# MCU.net
KiCad netlist of a schematic drawn in Altium Designer
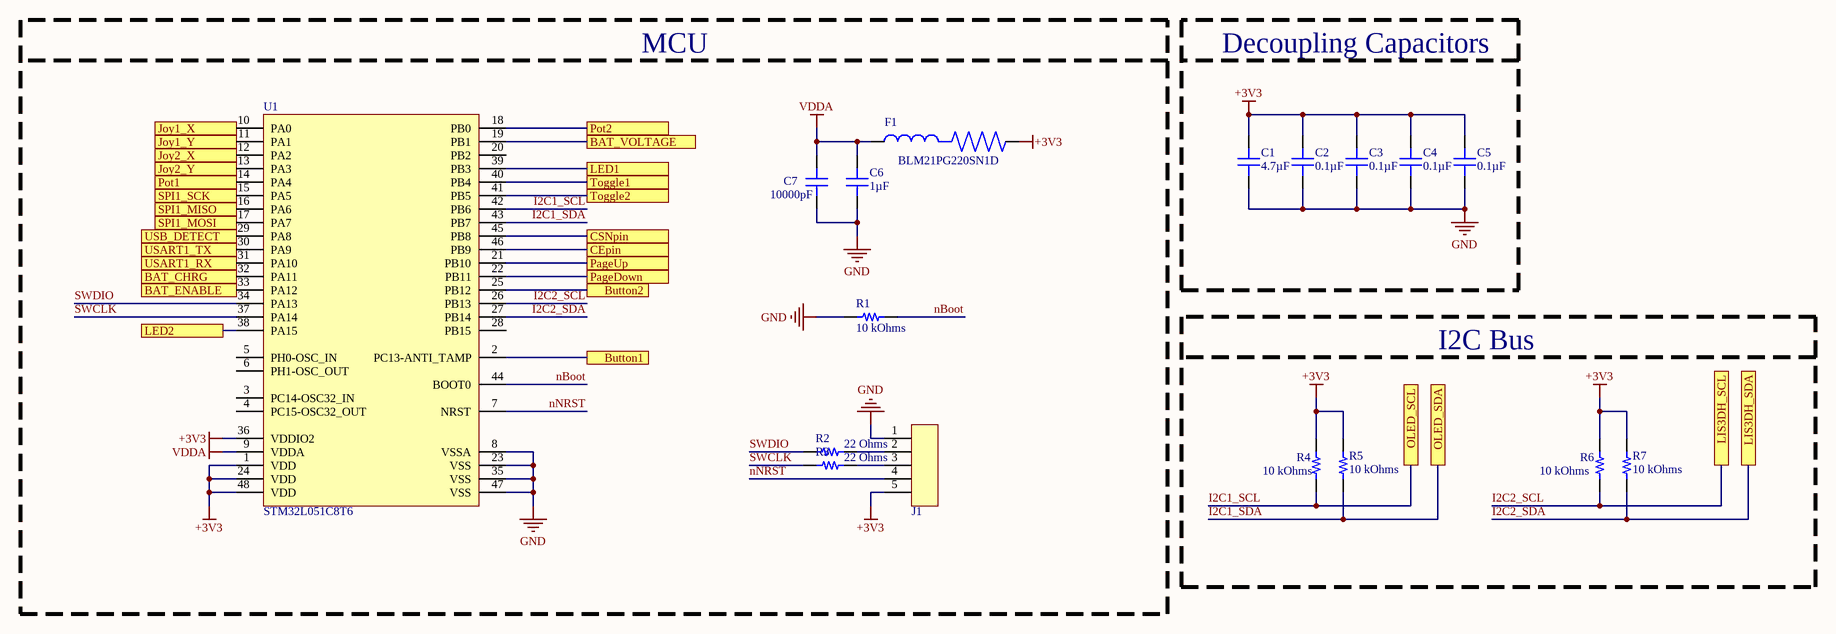
[diagram p0: MCU.SchDoc]

(export (version "E")
  (design (tool "Eeschema 10.0.6"))
  (components
    (comp (ref "C1")
      (value "4.7µF")
      (footprint "CAP 0603_1608")
      (description "CAP CER 4.7UF 10V X5R 0603")
      (fields (field (name "PART NUMBER") "LMK107BJ475KA-T") (field (name "MANUFACTURER") "Taiyo Yuden"))
      (libsource (lib "Celestial Altium Library - altium_library") (part "Capacitor"))
    )
    (comp (ref "C2")
      (value "0.1µF")
      (footprint "CAP 0603_1608")
      (description "CAP CER 0.10UF 16V X7R 0603")
      (fields (field (name "PART NUMBER") "0603Y0160104KXT") (field (name "MANUFACTURER") "Knowles Syfer"))
      (libsource (lib "Celestial Altium Library - altium_library") (part "Capacitor"))
    )
    (comp (ref "C3")
      (value "0.1µF")
      (footprint "CAP 0603_1608")
      (description "CAP CER 0.10UF 16V X7R 0603")
      (fields (field (name "PART NUMBER") "0603Y0160104KXT") (field (name "MANUFACTURER") "Knowles Syfer"))
      (libsource (lib "Celestial Altium Library - altium_library") (part "Capacitor"))
    )
    (comp (ref "C4")
      (value "0.1µF")
      (footprint "CAP 0603_1608")
      (description "CAP CER 0.10UF 16V X7R 0603")
      (fields (field (name "PART NUMBER") "0603Y0160104KXT") (field (name "MANUFACTURER") "Knowles Syfer"))
      (libsource (lib "Celestial Altium Library - altium_library") (part "Capacitor"))
    )
    (comp (ref "C5")
      (value "0.1µF")
      (footprint "CAP 0603_1608")
      (description "CAP CER 0.10UF 16V X7R 0603")
      (fields (field (name "PART NUMBER") "0603Y0160104KXT") (field (name "MANUFACTURER") "Knowles Syfer"))
      (libsource (lib "Celestial Altium Library - altium_library") (part "Capacitor"))
    )
    (comp (ref "C6")
      (value "1µF")
      (footprint "CAP 0603_1608")
      (description "CAP CER 0603 1UF 16V X7R 10%")
      (fields (field (name "PART NUMBER") "C0603C105K4RACAUTO") (field (name "MANUFACTURER") "KEMET"))
      (libsource (lib "Celestial Altium Library - altium_library") (part "Capacitor"))
    )
    (comp (ref "C7")
      (value "10000pF")
      (footprint "CAP 0603_1608")
      (description "CAP CER 0603 10NF 16V X7R 10%")
      (fields (field (name "PART NUMBER") "C0603C103K4RECAUTO") (field (name "MANUFACTURER") "KEMET"))
      (libsource (lib "Celestial Altium Library - altium_library") (part "Capacitor"))
    )
    (comp (ref "F1")
      (value "BLM21PG220SN1D")
      (footprint "BLM21PG220SN1D")
      (description "Ferrite Beads Multi-Layer 22Ohm 25% 100MHz 6A 9mOhm DCR 0805 Paper T/R")
      (fields (field (name "MANUFACTURER") "Murata") (field (name "TOLERANCE") "25%"))
      (libsource (lib "MyLibrary_Integrated") (part "BLM21PG220SN1D"))
    )
    (comp (ref "J1")
      (value "Header-90 Degree-5x1")
      (footprint "Header-90 Degree-5P")
      (libsource (lib "MyLibrary_Integrated") (part "Header-90 Degree-5x1"))
    )
    (comp (ref "R1")
      (value "10 kOhms")
      (footprint "RES 0603_1608")
      (description "RES 10K OHM 0.1% 1/16W 0603")
      (fields
        (field (name "PART NUMBER") "RNCS0603BKE10K0")
        (field (name "MANUFACTURER") "Stackpole Electronics Inc")
      )
      (libsource (lib "Celestial Altium Library - altium_library") (part "Resistor"))
    )
    (comp (ref "R2")
      (value "22 Ohms")
      (footprint "RES 0603_1608")
      (description "RES SMD 22 OHM 1% 1/10W 0603")
      (fields
        (field (name "PART NUMBER") "ERJ-3EKF22R0V")
        (field (name "MANUFACTURER") "Panasonic Electronic Components")
      )
      (libsource (lib "Celestial Altium Library - altium_library") (part "Resistor"))
    )
    (comp (ref "R3")
      (value "22 Ohms")
      (footprint "RES 0603_1608")
      (description "RES SMD 22 OHM 1% 1/10W 0603")
      (fields
        (field (name "PART NUMBER") "ERJ-3EKF22R0V")
        (field (name "MANUFACTURER") "Panasonic Electronic Components")
      )
      (libsource (lib "Celestial Altium Library - altium_library") (part "Resistor"))
    )
    (comp (ref "R4")
      (value "10 kOhms")
      (footprint "RES 0603_1608")
      (description "RES 10K OHM 0.1% 1/16W 0603")
      (fields
        (field (name "PART NUMBER") "RNCS0603BKE10K0")
        (field (name "MANUFACTURER") "Stackpole Electronics Inc")
      )
      (libsource (lib "Celestial Altium Library - altium_library") (part "Resistor"))
    )
    (comp (ref "R5")
      (value "10 kOhms")
      (footprint "RES 0603_1608")
      (description "RES 10K OHM 0.1% 1/16W 0603")
      (fields
        (field (name "PART NUMBER") "RNCS0603BKE10K0")
        (field (name "MANUFACTURER") "Stackpole Electronics Inc")
      )
      (libsource (lib "Celestial Altium Library - altium_library") (part "Resistor"))
    )
    (comp (ref "R6")
      (value "10 kOhms")
      (footprint "RES 0603_1608")
      (description "RES 10K OHM 0.1% 1/16W 0603")
      (fields
        (field (name "PART NUMBER") "RNCS0603BKE10K0")
        (field (name "MANUFACTURER") "Stackpole Electronics Inc")
      )
      (libsource (lib "Celestial Altium Library - altium_library") (part "Resistor"))
    )
    (comp (ref "R7")
      (value "10 kOhms")
      (footprint "RES 0603_1608")
      (description "RES 10K OHM 0.1% 1/16W 0603")
      (fields
        (field (name "PART NUMBER") "RNCS0603BKE10K0")
        (field (name "MANUFACTURER") "Stackpole Electronics Inc")
      )
      (libsource (lib "Celestial Altium Library - altium_library") (part "Resistor"))
    )
    (comp (ref "U1")
      (value "STM32L051C8T6")
      (footprint "LQFP-48")
      (description "MCU 32-Bit Ultra Low Power STM32L ARM Cortex M0+ RISC 64kB Flash 48-Pin LQFP Tray")
      (fields (field (name "MANUFACTURER") "STMicroelectronics"))
      (libsource (lib "MyLibrary_Integrated") (part "STM32L051C8T6"))
    )
  )
  (nets
    (net (code "1") (name "+3V3") (class "Default")
      (node (ref "C1") (pin "2") (pinfunction "2_2") (pintype "passive"))
      (node (ref "C2") (pin "2") (pinfunction "2_2") (pintype "passive"))
      (node (ref "C3") (pin "2") (pinfunction "2_2") (pintype "passive"))
      (node (ref "C4") (pin "2") (pinfunction "2_2") (pintype "passive"))
      (node (ref "C5") (pin "2") (pinfunction "2_2") (pintype "passive"))
      (node (ref "F1") (pin "2") (pinfunction "2_2") (pintype "passive"))
      (node (ref "J1") (pin "5") (pinfunction "4_5") (pintype "passive"))
      (node (ref "R4") (pin "2") (pinfunction "2_2") (pintype "passive"))
      (node (ref "R5") (pin "2") (pinfunction "2_2") (pintype "passive"))
      (node (ref "R6") (pin "2") (pinfunction "2_2") (pintype "passive"))
      (node (ref "R7") (pin "2") (pinfunction "2_2") (pintype "passive"))
      (node (ref "U1") (pin "1") (pinfunction "VDD_1") (pintype "power_in"))
      (node (ref "U1") (pin "24") (pinfunction "VDD_24") (pintype "power_in"))
      (node (ref "U1") (pin "36") (pinfunction "VDDIO2_36") (pintype "power_in"))
      (node (ref "U1") (pin "48") (pinfunction "VDD_48") (pintype "power_in"))
    )
    (net (code "2") (name "/BAT_CHRG") (class "Default")
      (node (ref "U1") (pin "32") (pinfunction "PA11_32") (pintype "passive"))
    )
    (net (code "3") (name "/BAT_ENABLE") (class "Default")
      (node (ref "U1") (pin "33") (pinfunction "PA12_33") (pintype "passive"))
    )
    (net (code "4") (name "/BAT_VOLTAGE") (class "Default")
      (node (ref "U1") (pin "19") (pinfunction "PB1_19") (pintype "passive"))
    )
    (net (code "5") (name "/Button1") (class "Default")
      (node (ref "U1") (pin "2") (pinfunction "PC13-ANTI_TAMP_2") (pintype "passive"))
    )
    (net (code "6") (name "/Button2") (class "Default")
      (node (ref "U1") (pin "25") (pinfunction "PB12_25") (pintype "passive"))
    )
    (net (code "7") (name "/CEpin") (class "Default")
      (node (ref "U1") (pin "46") (pinfunction "PB9_46") (pintype "passive"))
    )
    (net (code "8") (name "/CSNpin") (class "Default")
      (node (ref "U1") (pin "45") (pinfunction "PB8_45") (pintype "passive"))
    )
    (net (code "9") (name "/I2C1_SCL") (class "Default")
      (node (ref "R4") (pin "1") (pinfunction "1_1") (pintype "passive"))
      (node (ref "U1") (pin "42") (pinfunction "PB6_42") (pintype "passive"))
    )
    (net (code "10") (name "/I2C1_SDA") (class "Default")
      (node (ref "R5") (pin "1") (pinfunction "1_1") (pintype "passive"))
      (node (ref "U1") (pin "43") (pinfunction "PB7_43") (pintype "passive"))
    )
    (net (code "11") (name "/I2C2_SCL") (class "Default")
      (node (ref "R6") (pin "1") (pinfunction "1_1") (pintype "passive"))
      (node (ref "U1") (pin "26") (pinfunction "PB13_26") (pintype "passive"))
    )
    (net (code "12") (name "/I2C2_SDA") (class "Default")
      (node (ref "R7") (pin "1") (pinfunction "1_1") (pintype "passive"))
      (node (ref "U1") (pin "27") (pinfunction "PB14_27") (pintype "passive"))
    )
    (net (code "13") (name "/Joy1_X") (class "Default")
      (node (ref "U1") (pin "10") (pinfunction "PA0_10") (pintype "passive"))
    )
    (net (code "14") (name "/Joy1_Y") (class "Default")
      (node (ref "U1") (pin "11") (pinfunction "PA1_11") (pintype "passive"))
    )
    (net (code "15") (name "/Joy2_X") (class "Default")
      (node (ref "U1") (pin "12") (pinfunction "PA2_12") (pintype "passive"))
    )
    (net (code "16") (name "/Joy2_Y") (class "Default")
      (node (ref "U1") (pin "13") (pinfunction "PA3_13") (pintype "passive"))
    )
    (net (code "17") (name "/LED1") (class "Default")
      (node (ref "U1") (pin "39") (pinfunction "PB3_39") (pintype "passive"))
    )
    (net (code "18") (name "/LED2") (class "Default")
      (node (ref "U1") (pin "38") (pinfunction "PA15_38") (pintype "passive"))
    )
    (net (code "19") (name "/PageDown") (class "Default")
      (node (ref "U1") (pin "22") (pinfunction "PB11_22") (pintype "passive"))
    )
    (net (code "20") (name "/PageUp") (class "Default")
      (node (ref "U1") (pin "21") (pinfunction "PB10_21") (pintype "passive"))
    )
    (net (code "21") (name "/Pot1") (class "Default")
      (node (ref "U1") (pin "14") (pinfunction "PA4_14") (pintype "passive"))
    )
    (net (code "22") (name "/Pot2") (class "Default")
      (node (ref "U1") (pin "18") (pinfunction "PB0_18") (pintype "passive"))
    )
    (net (code "23") (name "/SPI1_MISO") (class "Default")
      (node (ref "U1") (pin "16") (pinfunction "PA6_16") (pintype "passive"))
    )
    (net (code "24") (name "/SPI1_MOSI") (class "Default")
      (node (ref "U1") (pin "17") (pinfunction "PA7_17") (pintype "passive"))
    )
    (net (code "25") (name "/SPI1_SCK") (class "Default")
      (node (ref "U1") (pin "15") (pinfunction "PA5_15") (pintype "passive"))
    )
    (net (code "26") (name "/SWCLK") (class "Default")
      (node (ref "R3") (pin "1") (pinfunction "1_1") (pintype "passive"))
      (node (ref "U1") (pin "37") (pinfunction "PA14_37") (pintype "passive"))
    )
    (net (code "27") (name "/SWDIO") (class "Default")
      (node (ref "R2") (pin "1") (pinfunction "1_1") (pintype "passive"))
      (node (ref "U1") (pin "34") (pinfunction "PA13_34") (pintype "passive"))
    )
    (net (code "28") (name "/Toggle1") (class "Default")
      (node (ref "U1") (pin "40") (pinfunction "PB4_40") (pintype "passive"))
    )
    (net (code "29") (name "/Toggle2") (class "Default")
      (node (ref "U1") (pin "41") (pinfunction "PB5_41") (pintype "passive"))
    )
    (net (code "30") (name "/USART1_RX") (class "Default")
      (node (ref "U1") (pin "31") (pinfunction "PA10_31") (pintype "passive"))
    )
    (net (code "31") (name "/USART1_TX") (class "Default")
      (node (ref "U1") (pin "30") (pinfunction "PA9_30") (pintype "passive"))
    )
    (net (code "32") (name "/USB_DETECT") (class "Default")
      (node (ref "U1") (pin "29") (pinfunction "PA8_29") (pintype "passive"))
    )
    (net (code "33") (name "/nBoot") (class "Default")
      (node (ref "R1") (pin "2") (pinfunction "2_2") (pintype "passive"))
      (node (ref "U1") (pin "44") (pinfunction "BOOT0_44") (pintype "passive"))
    )
    (net (code "34") (name "/nNRST") (class "Default")
      (node (ref "J1") (pin "4") (pinfunction "3_4") (pintype "passive"))
      (node (ref "U1") (pin "7") (pinfunction "NRST_7") (pintype "passive"))
    )
    (net (code "35") (name "GND") (class "Default")
      (node (ref "C1") (pin "1") (pinfunction "1_1") (pintype "passive"))
      (node (ref "C2") (pin "1") (pinfunction "1_1") (pintype "passive"))
      (node (ref "C3") (pin "1") (pinfunction "1_1") (pintype "passive"))
      (node (ref "C4") (pin "1") (pinfunction "1_1") (pintype "passive"))
      (node (ref "C5") (pin "1") (pinfunction "1_1") (pintype "passive"))
      (node (ref "C6") (pin "1") (pinfunction "1_1") (pintype "passive"))
      (node (ref "C7") (pin "1") (pinfunction "1_1") (pintype "passive"))
      (node (ref "J1") (pin "1") (pinfunction "0_1") (pintype "passive"))
      (node (ref "R1") (pin "1") (pinfunction "1_1") (pintype "passive"))
      (node (ref "U1") (pin "23") (pinfunction "VSS_23") (pintype "power_in"))
      (node (ref "U1") (pin "35") (pinfunction "VSS_35") (pintype "power_in"))
      (node (ref "U1") (pin "47") (pinfunction "VSS_47") (pintype "power_in"))
      (node (ref "U1") (pin "8") (pinfunction "VSSA_8") (pintype "power_in"))
    )
    (net (code "36") (name "Net-(J1-1)") (class "Default")
      (node (ref "J1") (pin "2") (pinfunction "1_2") (pintype "passive"))
      (node (ref "R2") (pin "2") (pinfunction "2_2") (pintype "passive"))
    )
    (net (code "37") (name "Net-(J1-2)") (class "Default")
      (node (ref "J1") (pin "3") (pinfunction "2_3") (pintype "passive"))
      (node (ref "R3") (pin "2") (pinfunction "2_2") (pintype "passive"))
    )
    (net (code "38") (name "VDDA") (class "Default")
      (node (ref "C6") (pin "2") (pinfunction "2_2") (pintype "passive"))
      (node (ref "C7") (pin "2") (pinfunction "2_2") (pintype "passive"))
      (node (ref "F1") (pin "1") (pinfunction "1_1") (pintype "passive"))
      (node (ref "U1") (pin "9") (pinfunction "VDDA_9") (pintype "power_in"))
    )
    (net (code "39") (name "unconnected-(U1-PB2-Pad20)") (class "Default")
      (node (ref "U1") (pin "20") (pinfunction "PB2_20") (pintype "passive"))
    )
    (net (code "40") (name "unconnected-(U1-PB15-Pad28)") (class "Default")
      (node (ref "U1") (pin "28") (pinfunction "PB15_28") (pintype "passive"))
    )
    (net (code "41") (name "unconnected-(U1-PC14-OSC32_IN-Pad3)") (class "Default")
      (node (ref "U1") (pin "3") (pinfunction "PC14-OSC32_IN_3") (pintype "passive"))
    )
    (net (code "42") (name "unconnected-(U1-PC15-OSC32_OUT-Pad4)") (class "Default")
      (node (ref "U1") (pin "4") (pinfunction "PC15-OSC32_OUT_4") (pintype "passive"))
    )
    (net (code "43") (name "unconnected-(U1-PH0-OSC_IN-Pad5)") (class "Default")
      (node (ref "U1") (pin "5") (pinfunction "PH0-OSC_IN_5") (pintype "passive"))
    )
    (net (code "44") (name "unconnected-(U1-PH1-OSC_OUT-Pad6)") (class "Default")
      (node (ref "U1") (pin "6") (pinfunction "PH1-OSC_OUT_6") (pintype "passive"))
    )
  )
)
